# Encoders_In.net
KiCad netlist of a schematic drawn in Altium Designer
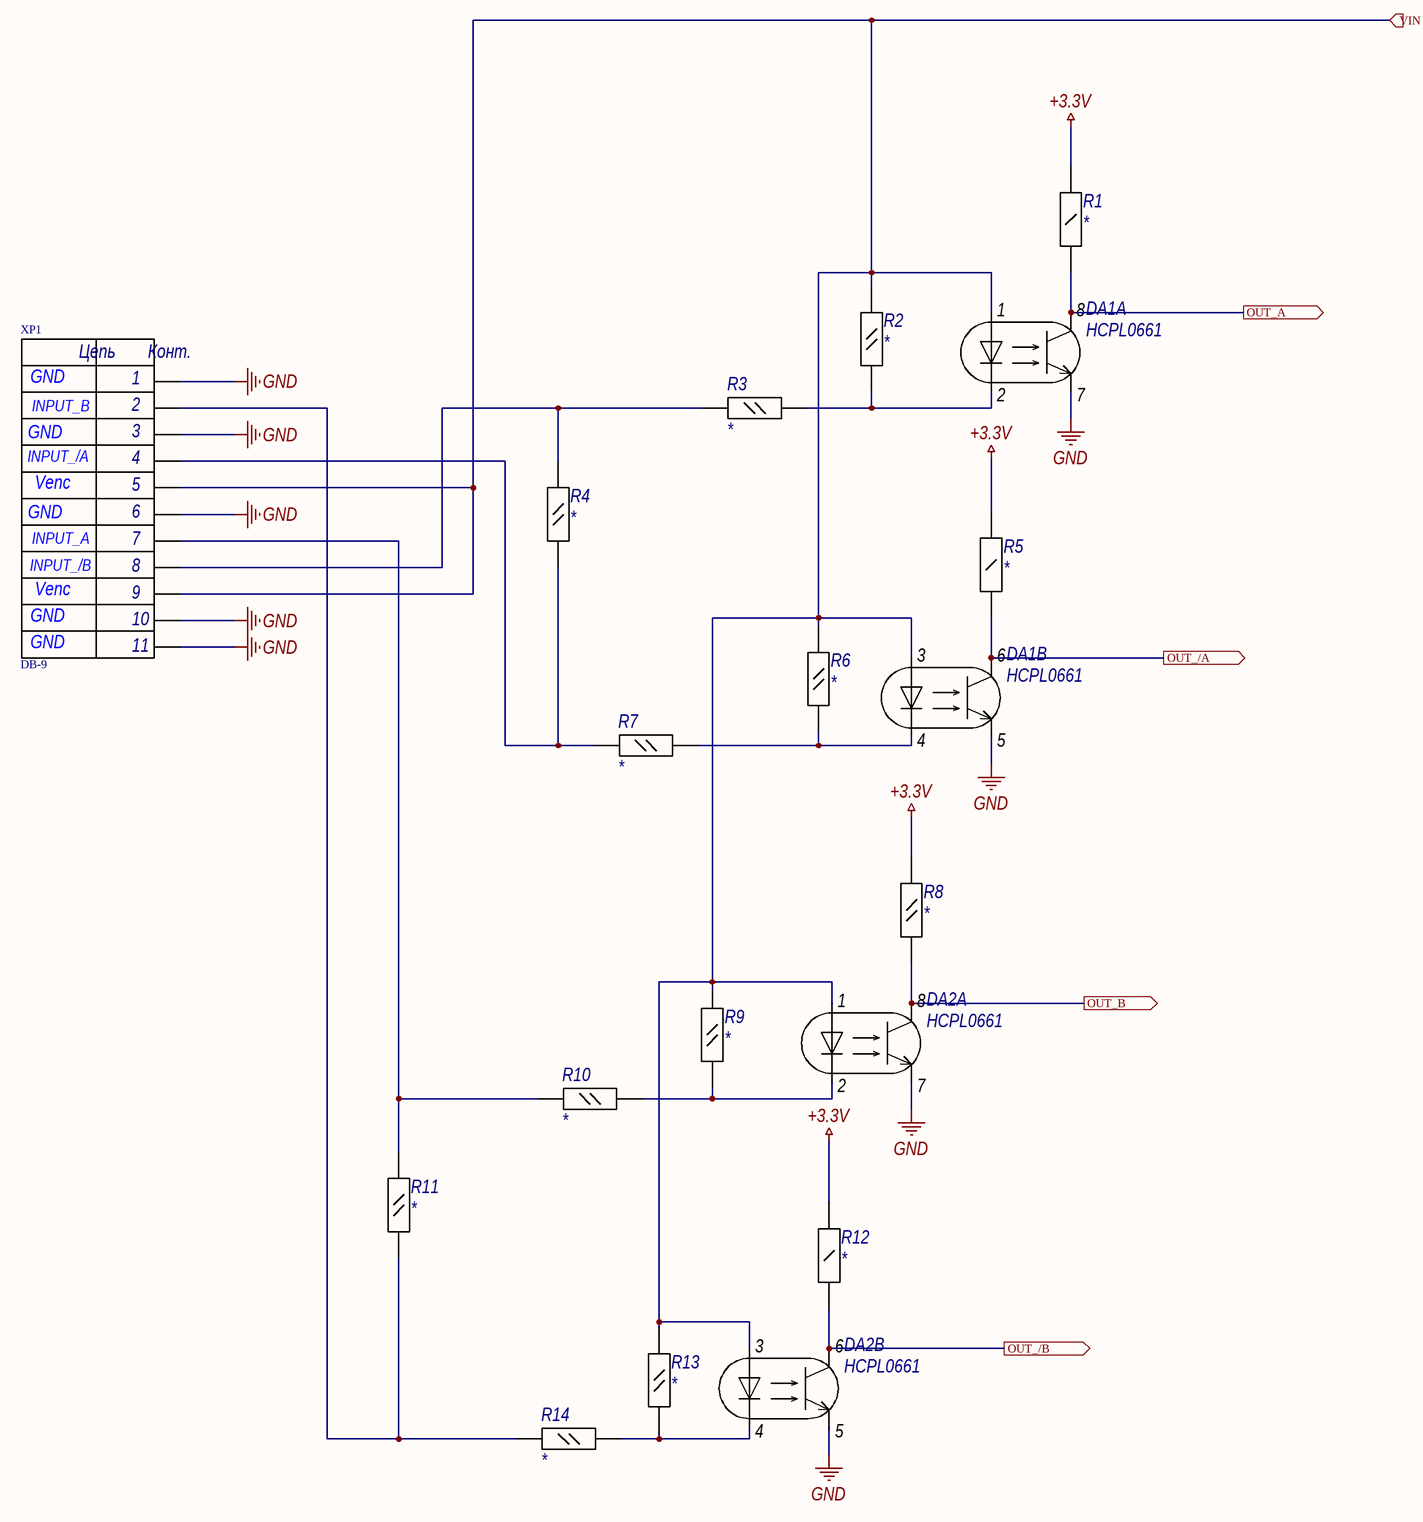
[diagram p0: Encoders_In.SchDoc]

(export (version "E")
  (design (tool "Eeschema 10.0.6"))
  (components
    (comp (ref "DA1")
      (value "HCPL0661")
      (footprint "DX_test_PcbLib1:SO8N_MS012AA-II")
      (description "Оптопара 2 канала")
      (fields (field (name "MANUFACTURER") "HP"))
      (libsource (lib "DX_test_lib2") (part "HCPL0661"))
    )
    (comp (ref "DA2")
      (value "HCPL0661")
      (footprint "DX_test_PcbLib1:SO8N_MS012AA-II")
      (description "Оптопара 2 канала")
      (fields (field (name "MANUFACTURER") "HP"))
      (libsource (lib "DX_test_lib2") (part "HCPL0661"))
    )
    (comp (ref "R1") (value "*") (footprint "1206") (libsource (lib "Resistors") (part "CRCW1206")))
    (comp (ref "R2")
      (value "*")
      (footprint "0805")
      (description "Резистор общего назначения 5%")
      (fields (field (name "MANUFACTURER") "YAGEO"))
      (libsource (lib "DX_test_lib2") (part "RC0805JR"))
    )
    (comp (ref "R3")
      (value "*")
      (footprint "0805")
      (description "Резистор общего назначения 5%")
      (fields (field (name "MANUFACTURER") "YAGEO"))
      (libsource (lib "DX_test_lib2") (part "RC0805JR"))
    )
    (comp (ref "R4")
      (value "*")
      (footprint "0805")
      (description "Резистор общего назначения 5%")
      (fields (field (name "MANUFACTURER") "YAGEO"))
      (libsource (lib "DX_test_lib2") (part "RC0805JR"))
    )
    (comp (ref "R5") (value "*") (footprint "1206") (libsource (lib "Resistors") (part "CRCW1206")))
    (comp (ref "R6")
      (value "*")
      (footprint "0805")
      (description "Резистор общего назначения 5%")
      (fields (field (name "MANUFACTURER") "YAGEO"))
      (libsource (lib "DX_test_lib2") (part "RC0805JR"))
    )
    (comp (ref "R7")
      (value "*")
      (footprint "0805")
      (description "Резистор общего назначения 5%")
      (fields (field (name "MANUFACTURER") "YAGEO"))
      (libsource (lib "DX_test_lib2") (part "RC0805JR"))
    )
    (comp (ref "R8")
      (value "*")
      (footprint "0805")
      (description "Резистор общего назначения 5%")
      (fields (field (name "MANUFACTURER") "YAGEO"))
      (libsource (lib "DX_test_lib2") (part "RC0805JR"))
    )
    (comp (ref "R9")
      (value "*")
      (footprint "0805")
      (description "Резистор общего назначения 5%")
      (fields (field (name "MANUFACTURER") "YAGEO"))
      (libsource (lib "DX_test_lib2") (part "RC0805JR"))
    )
    (comp (ref "R10")
      (value "*")
      (footprint "0805")
      (description "Резистор общего назначения 5%")
      (fields (field (name "MANUFACTURER") "YAGEO"))
      (libsource (lib "DX_test_lib2") (part "RC0805JR"))
    )
    (comp (ref "R11")
      (value "*")
      (footprint "0805")
      (description "Резистор общего назначения 5%")
      (fields (field (name "MANUFACTURER") "YAGEO"))
      (libsource (lib "DX_test_lib2") (part "RC0805JR"))
    )
    (comp (ref "R12") (value "*") (footprint "1206") (libsource (lib "Resistors") (part "CRCW1206")))
    (comp (ref "R13")
      (value "*")
      (footprint "0805")
      (description "Резистор общего назначения 5%")
      (fields (field (name "MANUFACTURER") "YAGEO"))
      (libsource (lib "DX_test_lib2") (part "RC0805JR"))
    )
    (comp (ref "R14")
      (value "*")
      (footprint "0805")
      (description "Резистор общего назначения 5%")
      (fields (field (name "MANUFACTURER") "YAGEO"))
      (libsource (lib "DX_test_lib2") (part "RC0805JR"))
    )
    (comp (ref "XP1")
      (value "DB-9")
      (footprint "DB-9M")
      (description "Connector DB-9")
      (libsource (lib "DX_test_lib2") (part "DB-9"))
    )
  )
  (nets
    (net (code "1") (name "+3.3V") (class "Default")
      (node (ref "R1") (pin "2") (pinfunction "2_2") (pintype "passive"))
      (node (ref "R12") (pin "2") (pinfunction "2_2") (pintype "passive"))
      (node (ref "R5") (pin "2") (pinfunction "2_2") (pintype "passive"))
      (node (ref "R8") (pin "2") (pinfunction "2_2") (pintype "passive"))
    )
    (net (code "2") (name "/OUT_A") (class "Default")
      (node (ref "DA1") (pin "8") (pinfunction "C1_8") (pintype "passive"))
      (node (ref "R1") (pin "1") (pinfunction "1_1") (pintype "passive"))
    )
    (net (code "3") (name "/OUT_B") (class "Default")
      (node (ref "DA2") (pin "8") (pinfunction "C1_8") (pintype "passive"))
      (node (ref "R8") (pin "1") (pinfunction "1_1") (pintype "passive"))
    )
    (net (code "4") (name "/OUT_{slash}A") (class "Default")
      (node (ref "DA1") (pin "6") (pinfunction "C2_6") (pintype "passive"))
      (node (ref "R5") (pin "1") (pinfunction "1_1") (pintype "passive"))
    )
    (net (code "5") (name "/OUT_{slash}B") (class "Default")
      (node (ref "DA2") (pin "6") (pinfunction "C2_6") (pintype "passive"))
      (node (ref "R12") (pin "1") (pinfunction "1_1") (pintype "passive"))
    )
    (net (code "6") (name "/VIN") (class "Default")
      (node (ref "DA1") (pin "1") (pinfunction "ANODE1_1") (pintype "passive"))
      (node (ref "DA1") (pin "3") (pinfunction "ANODE2_3") (pintype "passive"))
      (node (ref "DA2") (pin "1") (pinfunction "ANODE1_1") (pintype "passive"))
      (node (ref "DA2") (pin "3") (pinfunction "ANODE2_3") (pintype "passive"))
      (node (ref "R13") (pin "2") (pinfunction "2_2") (pintype "passive"))
      (node (ref "R2") (pin "2") (pinfunction "2_2") (pintype "passive"))
      (node (ref "R6") (pin "2") (pinfunction "2_2") (pintype "passive"))
      (node (ref "R9") (pin "2") (pinfunction "2_2") (pintype "passive"))
      (node (ref "XP1") (pin "5") (pinfunction "5_5") (pintype "passive"))
      (node (ref "XP1") (pin "9") (pinfunction "9_9") (pintype "passive"))
    )
    (net (code "7") (name "GND") (class "Default")
      (node (ref "DA1") (pin "5") (pinfunction "E2_5") (pintype "passive"))
      (node (ref "DA1") (pin "7") (pinfunction "E1_7") (pintype "passive"))
      (node (ref "DA2") (pin "5") (pinfunction "E2_5") (pintype "passive"))
      (node (ref "DA2") (pin "7") (pinfunction "E1_7") (pintype "passive"))
      (node (ref "XP1") (pin "1") (pinfunction "1_1") (pintype "passive"))
      (node (ref "XP1") (pin "10") (pinfunction "10_10") (pintype "passive"))
      (node (ref "XP1") (pin "11") (pinfunction "11_11") (pintype "passive"))
      (node (ref "XP1") (pin "3") (pinfunction "3_3") (pintype "passive"))
      (node (ref "XP1") (pin "6") (pinfunction "6_6") (pintype "passive"))
    )
    (net (code "8") (name "Net-(DA1A-CATHODE1)") (class "Default")
      (node (ref "DA1") (pin "2") (pinfunction "CATHODE1_2") (pintype "passive"))
      (node (ref "R2") (pin "1") (pinfunction "1_1") (pintype "passive"))
      (node (ref "R3") (pin "2") (pinfunction "2_2") (pintype "passive"))
    )
    (net (code "9") (name "Net-(DA1B-CATHODE2)") (class "Default")
      (node (ref "DA1") (pin "4") (pinfunction "CATHODE2_4") (pintype "passive"))
      (node (ref "R6") (pin "1") (pinfunction "1_1") (pintype "passive"))
      (node (ref "R7") (pin "2") (pinfunction "2_2") (pintype "passive"))
    )
    (net (code "10") (name "Net-(DA2A-CATHODE1)") (class "Default")
      (node (ref "DA2") (pin "2") (pinfunction "CATHODE1_2") (pintype "passive"))
      (node (ref "R10") (pin "2") (pinfunction "2_2") (pintype "passive"))
      (node (ref "R9") (pin "1") (pinfunction "1_1") (pintype "passive"))
    )
    (net (code "11") (name "Net-(DA2B-CATHODE2)") (class "Default")
      (node (ref "DA2") (pin "4") (pinfunction "CATHODE2_4") (pintype "passive"))
      (node (ref "R13") (pin "1") (pinfunction "1_1") (pintype "passive"))
      (node (ref "R14") (pin "2") (pinfunction "2_2") (pintype "passive"))
    )
    (net (code "12") (name "Net-(R3-Pad1)") (class "Default")
      (node (ref "R3") (pin "1") (pinfunction "1_1") (pintype "passive"))
      (node (ref "R4") (pin "2") (pinfunction "2_2") (pintype "passive"))
      (node (ref "XP1") (pin "8") (pinfunction "8_8") (pintype "passive"))
    )
    (net (code "13") (name "Net-(R4-Pad1)") (class "Default")
      (node (ref "R4") (pin "1") (pinfunction "1_1") (pintype "passive"))
      (node (ref "R7") (pin "1") (pinfunction "1_1") (pintype "passive"))
      (node (ref "XP1") (pin "4") (pinfunction "4_4") (pintype "passive"))
    )
    (net (code "14") (name "Net-(R10-Pad1)") (class "Default")
      (node (ref "R10") (pin "1") (pinfunction "1_1") (pintype "passive"))
      (node (ref "R11") (pin "2") (pinfunction "2_2") (pintype "passive"))
      (node (ref "XP1") (pin "7") (pinfunction "7_7") (pintype "passive"))
    )
    (net (code "15") (name "Net-(R11-Pad1)") (class "Default")
      (node (ref "R11") (pin "1") (pinfunction "1_1") (pintype "passive"))
      (node (ref "R14") (pin "1") (pinfunction "1_1") (pintype "passive"))
      (node (ref "XP1") (pin "2") (pinfunction "2_2") (pintype "passive"))
    )
  )
)
